# RaspiLabBoard.net
KiCad netlist of a schematic drawn in EAGLE
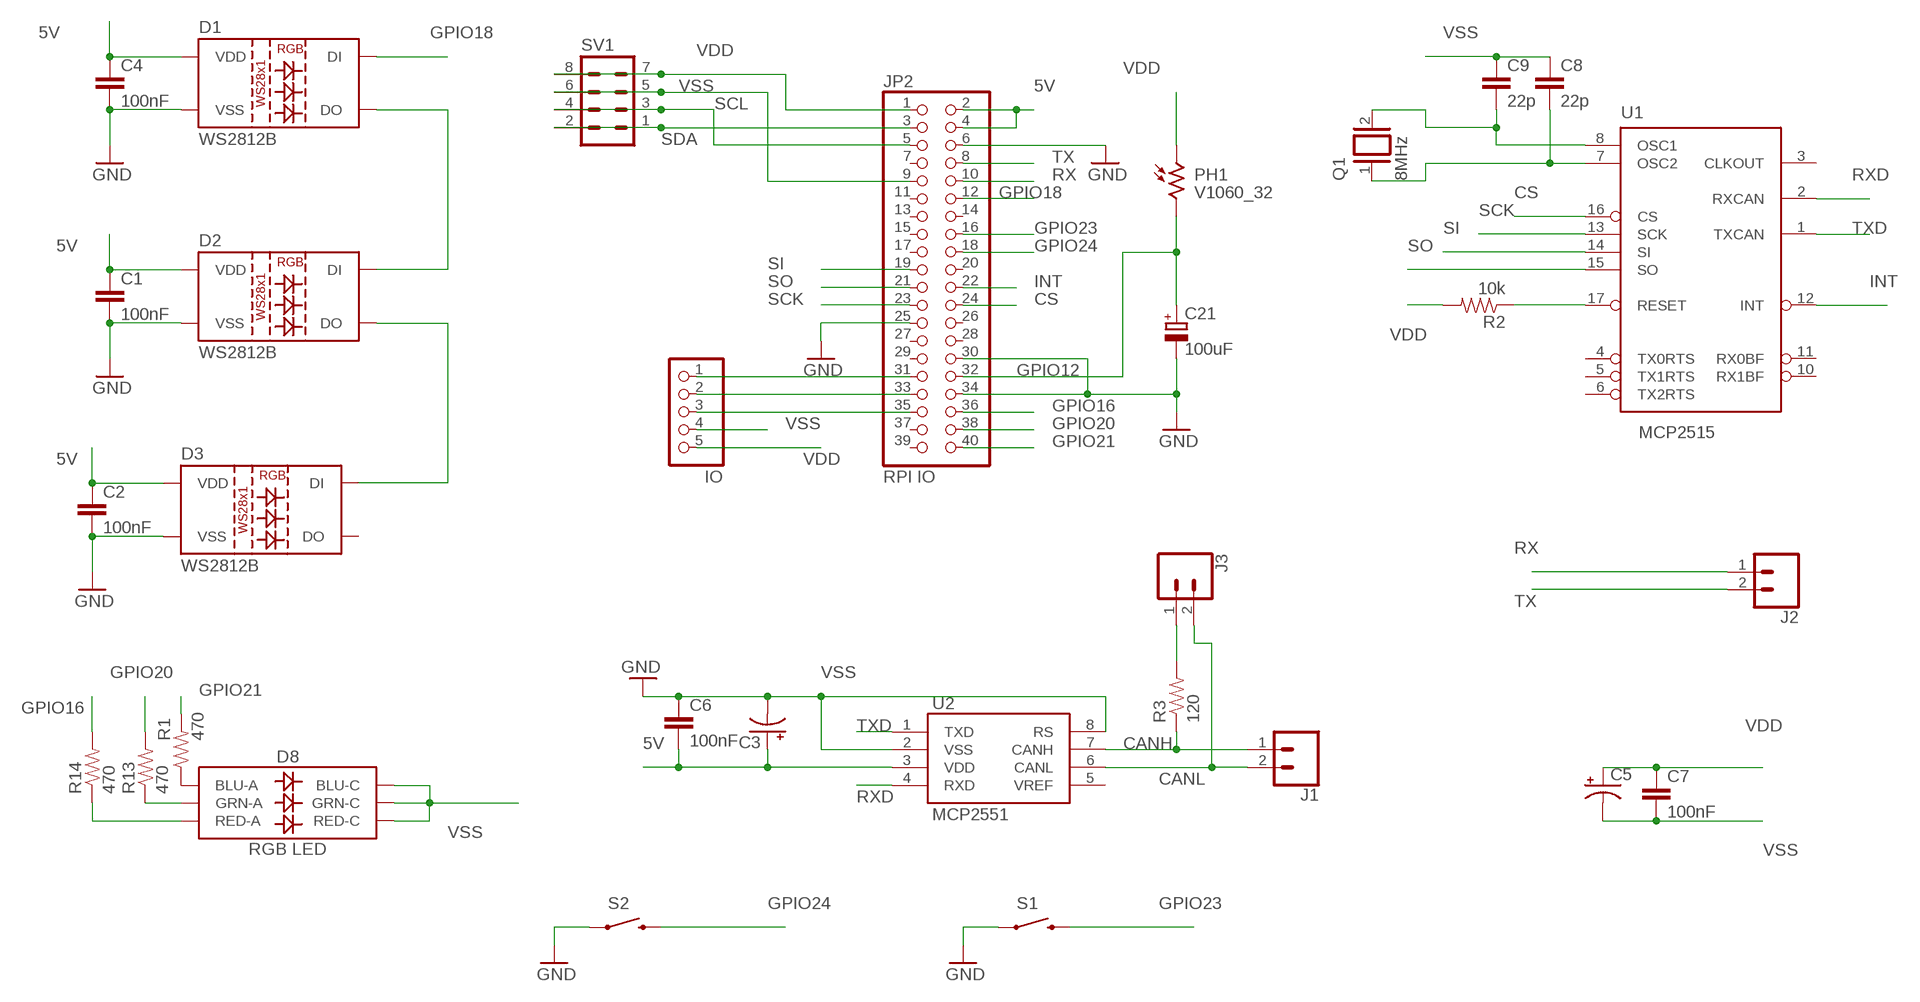
[diagram p0: schematic, sheet 1]

(export (version "E")
  (design (tool "Eeschema 10.0.6"))
  (components
    (comp (ref "C1")
      (value "100nF")
      (footprint "eagle-import:0805")
      (libsource (lib "eagle-import") (part "CAP0805"))
    )
    (comp (ref "C2")
      (value "100nF")
      (footprint "eagle-import:0805")
      (libsource (lib "eagle-import") (part "CAP0805"))
    )
    (comp (ref "C3")
      (value "CPOL-USE2-5")
      (footprint "eagle-import:E2-5")
      (libsource (lib "eagle-import") (part "CPOL-USE2-5"))
    )
    (comp (ref "C4")
      (value "100nF")
      (footprint "eagle-import:0805")
      (libsource (lib "eagle-import") (part "CAP0805"))
    )
    (comp (ref "C5")
      (value "CPOL-USE2-5")
      (footprint "eagle-import:E2-5")
      (libsource (lib "eagle-import") (part "CPOL-USE2-5"))
    )
    (comp (ref "C6")
      (value "100nF")
      (footprint "eagle-import:0805")
      (libsource (lib "eagle-import") (part "CAP0805"))
    )
    (comp (ref "C7")
      (value "100nF")
      (footprint "eagle-import:0805")
      (libsource (lib "eagle-import") (part "CAP0805"))
    )
    (comp (ref "C8")
      (value "22p")
      (footprint "eagle-import:0805")
      (libsource (lib "eagle-import") (part "CAP0805"))
    )
    (comp (ref "C9")
      (value "22p")
      (footprint "eagle-import:0805")
      (libsource (lib "eagle-import") (part "CAP0805"))
    )
    (comp (ref "C21")
      (value "100uF")
      (footprint "eagle-import:E5-10,5")
      (libsource (lib "eagle-import") (part "CPOL-EUE5-10.5"))
    )
    (comp (ref "D1")
      (value "WS2812B")
      (footprint "eagle-import:WS2812B")
      (libsource (lib "eagle-import") (part "WS2812B"))
    )
    (comp (ref "D2")
      (value "WS2812B")
      (footprint "eagle-import:WS2812B")
      (libsource (lib "eagle-import") (part "WS2812B"))
    )
    (comp (ref "D3")
      (value "WS2812B")
      (footprint "eagle-import:WS2812B")
      (libsource (lib "eagle-import") (part "WS2812B"))
    )
    (comp (ref "D8")
      (value "RGB LED")
      (footprint "eagle-import:LED-TRICOLOR-5050")
      (libsource (lib "eagle-import") (part "LED-RGBNO_IC"))
    )
    (comp (ref "J1")
      (value "CONN_02")
      (footprint "eagle-import:1X02")
      (libsource (lib "eagle-import") (part "CONN_02"))
    )
    (comp (ref "J2")
      (value "CONN_02")
      (footprint "eagle-import:1X02")
      (libsource (lib "eagle-import") (part "CONN_02"))
    )
    (comp (ref "J3")
      (value "CONN_02")
      (footprint "eagle-import:1X02")
      (libsource (lib "eagle-import") (part "CONN_02"))
    )
    (comp (ref "JP2")
      (value "RPI IO")
      (footprint "eagle-import:2X20")
      (libsource (lib "eagle-import") (part "PINHD-2X20"))
    )
    (comp (ref "JP4")
      (value "IO")
      (footprint "eagle-import:1X05")
      (libsource (lib "eagle-import") (part "PINHD-1X5"))
    )
    (comp (ref "PH1")
      (value "V1060_32")
      (footprint "eagle-import:TO-5_V10")
      (libsource (lib "eagle-import") (part "?1060V_32"))
    )
    (comp (ref "Q1")
      (value "8MHz")
      (footprint "eagle-import:QS")
      (libsource (lib "eagle-import") (part "XTAL/S"))
    )
    (comp (ref "R1")
      (value "470")
      (footprint "eagle-import:0805")
      (libsource (lib "eagle-import") (part "RESISTOR0805-RES"))
    )
    (comp (ref "R2")
      (value "10k")
      (footprint "eagle-import:0805")
      (libsource (lib "eagle-import") (part "RESISTOR0805-RES"))
    )
    (comp (ref "R3")
      (value "120")
      (footprint "eagle-import:0805")
      (libsource (lib "eagle-import") (part "RESISTOR0805-RES"))
    )
    (comp (ref "R13")
      (value "470")
      (footprint "eagle-import:0805")
      (libsource (lib "eagle-import") (part "RESISTOR0805-RES"))
    )
    (comp (ref "R14")
      (value "470")
      (footprint "eagle-import:0805")
      (libsource (lib "eagle-import") (part "RESISTOR0805-RES"))
    )
    (comp (ref "S1")
      (value "RESET")
      (footprint "eagle-import:TACTILE-SWITCH-1101NE")
      (libsource (lib "eagle-import") (part "SWITCH-MOMENTARY-2SMD-1101NE"))
    )
    (comp (ref "S2")
      (value "RESET")
      (footprint "eagle-import:TACTILE-SWITCH-1101NE")
      (libsource (lib "eagle-import") (part "SWITCH-MOMENTARY-2SMD-1101NE"))
    )
    (comp (ref "SV1")
      (value "MA04-2")
      (footprint "eagle-import:MA04-2")
      (libsource (lib "eagle-import") (part "MA04-2"))
    )
    (comp (ref "U1")
      (value "MCP2515")
      (footprint "eagle-import:SO18W")
      (fields (field (name "SPICEPREFIX") "X"))
      (libsource (lib "eagle-import") (part "MCP2515(MCP2510)SO"))
    )
    (comp (ref "U2")
      (value "MCP2551")
      (footprint "eagle-import:SO08")
      (libsource (lib "eagle-import") (part "MCP2551"))
    )
  )
  (nets
    (net (code "1") (name "/5V") (class "Default")
      (node (ref "C1") (pin "1") (pinfunction "1_1") (pintype "passive"))
      (node (ref "C2") (pin "1") (pinfunction "1_1") (pintype "passive"))
      (node (ref "C3") (pin "+") (pinfunction "+_+") (pintype "passive"))
      (node (ref "C4") (pin "1") (pinfunction "1_1") (pintype "passive"))
      (node (ref "C6") (pin "2") (pinfunction "2_2") (pintype "passive"))
      (node (ref "D1") (pin "1") (pinfunction "VDD_1") (pintype "bidirectional"))
      (node (ref "D2") (pin "1") (pinfunction "VDD_1") (pintype "bidirectional"))
      (node (ref "D3") (pin "1") (pinfunction "VDD_1") (pintype "bidirectional"))
      (node (ref "JP2") (pin "2") (pinfunction "2_2") (pintype "passive"))
      (node (ref "JP2") (pin "4") (pinfunction "4_4") (pintype "passive"))
      (node (ref "U2") (pin "3") (pinfunction "VDD_3") (pintype "bidirectional"))
    )
    (net (code "2") (name "/CANH") (class "Default")
      (node (ref "J1") (pin "1") (pinfunction "1_1") (pintype "passive"))
      (node (ref "R3") (pin "1") (pinfunction "1_1") (pintype "passive"))
      (node (ref "U2") (pin "7") (pinfunction "CANH_7") (pintype "bidirectional"))
    )
    (net (code "3") (name "/CANL") (class "Default")
      (node (ref "J1") (pin "2") (pinfunction "2_2") (pintype "passive"))
      (node (ref "J3") (pin "2") (pinfunction "2_2") (pintype "passive"))
      (node (ref "U2") (pin "6") (pinfunction "CANL_6") (pintype "bidirectional"))
    )
    (net (code "4") (name "/CS") (class "Default")
      (node (ref "JP2") (pin "24") (pinfunction "24_24") (pintype "passive"))
      (node (ref "U1") (pin "16") (pinfunction "CS_16") (pintype "input"))
    )
    (net (code "5") (name "/GPIO12") (class "Default")
      (node (ref "C21") (pin "+") (pinfunction "+_+") (pintype "passive"))
      (node (ref "JP2") (pin "32") (pinfunction "32_32") (pintype "passive"))
      (node (ref "PH1") (pin "2") (pinfunction "2_2") (pintype "passive"))
    )
    (net (code "6") (name "/GPIO16") (class "Default")
      (node (ref "JP2") (pin "36") (pinfunction "36_36") (pintype "passive"))
      (node (ref "R14") (pin "2") (pinfunction "2_2") (pintype "passive"))
    )
    (net (code "7") (name "/GPIO18") (class "Default")
      (node (ref "D1") (pin "4") (pinfunction "DI_4") (pintype "bidirectional"))
      (node (ref "JP2") (pin "12") (pinfunction "12_12") (pintype "passive"))
    )
    (net (code "8") (name "/GPIO20") (class "Default")
      (node (ref "JP2") (pin "38") (pinfunction "38_38") (pintype "passive"))
      (node (ref "R13") (pin "2") (pinfunction "2_2") (pintype "passive"))
    )
    (net (code "9") (name "/GPIO21") (class "Default")
      (node (ref "JP2") (pin "40") (pinfunction "40_40") (pintype "passive"))
      (node (ref "R1") (pin "2") (pinfunction "2_2") (pintype "passive"))
    )
    (net (code "10") (name "/GPIO23") (class "Default")
      (node (ref "JP2") (pin "16") (pinfunction "16_16") (pintype "passive"))
      (node (ref "S1") (pin "2") (pinfunction "2_2") (pintype "passive"))
    )
    (net (code "11") (name "/GPIO24") (class "Default")
      (node (ref "JP2") (pin "18") (pinfunction "18_18") (pintype "passive"))
      (node (ref "S2") (pin "2") (pinfunction "2_2") (pintype "passive"))
    )
    (net (code "12") (name "/INT") (class "Default")
      (node (ref "JP2") (pin "22") (pinfunction "22_22") (pintype "passive"))
      (node (ref "U1") (pin "12") (pinfunction "INT_12") (pintype "output"))
    )
    (net (code "13") (name "/RX") (class "Default")
      (node (ref "J2") (pin "1") (pinfunction "1_1") (pintype "passive"))
      (node (ref "JP2") (pin "10") (pinfunction "10_10") (pintype "passive"))
    )
    (net (code "14") (name "/RXD") (class "Default")
      (node (ref "U1") (pin "2") (pinfunction "RXCAN_2") (pintype "input"))
      (node (ref "U2") (pin "4") (pinfunction "RXD_4") (pintype "bidirectional"))
    )
    (net (code "15") (name "/SCK") (class "Default")
      (node (ref "JP2") (pin "23") (pinfunction "23_23") (pintype "passive"))
      (node (ref "U1") (pin "13") (pinfunction "SCK_13") (pintype "input"))
    )
    (net (code "16") (name "/SCL") (class "Default")
      (node (ref "JP2") (pin "5") (pinfunction "5_5") (pintype "passive"))
      (node (ref "SV1") (pin "3") (pinfunction "3_3") (pintype "passive"))
      (node (ref "SV1") (pin "4") (pinfunction "4_4") (pintype "passive"))
    )
    (net (code "17") (name "/SDA") (class "Default")
      (node (ref "JP2") (pin "3") (pinfunction "3_3") (pintype "passive"))
      (node (ref "SV1") (pin "1") (pinfunction "1_1") (pintype "passive"))
      (node (ref "SV1") (pin "2") (pinfunction "2_2") (pintype "passive"))
    )
    (net (code "18") (name "/SI") (class "Default")
      (node (ref "JP2") (pin "19") (pinfunction "19_19") (pintype "passive"))
      (node (ref "U1") (pin "14") (pinfunction "SI_14") (pintype "input"))
    )
    (net (code "19") (name "/SO") (class "Default")
      (node (ref "JP2") (pin "21") (pinfunction "21_21") (pintype "passive"))
      (node (ref "U1") (pin "15") (pinfunction "SO_15") (pintype "output"))
    )
    (net (code "20") (name "/TX") (class "Default")
      (node (ref "J2") (pin "2") (pinfunction "2_2") (pintype "passive"))
      (node (ref "JP2") (pin "8") (pinfunction "8_8") (pintype "passive"))
    )
    (net (code "21") (name "/TXD") (class "Default")
      (node (ref "U1") (pin "1") (pinfunction "TXCAN_1") (pintype "output"))
      (node (ref "U2") (pin "1") (pinfunction "TXD_1") (pintype "bidirectional"))
    )
    (net (code "22") (name "/VDD") (class "Default")
      (node (ref "C5") (pin "+") (pinfunction "+_+") (pintype "passive"))
      (node (ref "C7") (pin "1") (pinfunction "1_1") (pintype "passive"))
      (node (ref "JP2") (pin "1") (pinfunction "1_1") (pintype "passive"))
      (node (ref "JP4") (pin "5") (pinfunction "5_5") (pintype "passive"))
      (node (ref "PH1") (pin "1") (pinfunction "1_1") (pintype "passive"))
      (node (ref "R2") (pin "2") (pinfunction "2_2") (pintype "passive"))
      (node (ref "SV1") (pin "7") (pinfunction "7_7") (pintype "passive"))
      (node (ref "SV1") (pin "8") (pinfunction "8_8") (pintype "passive"))
    )
    (net (code "23") (name "GND") (class "Default")
      (node (ref "C1") (pin "2") (pinfunction "2_2") (pintype "passive"))
      (node (ref "C2") (pin "2") (pinfunction "2_2") (pintype "passive"))
      (node (ref "C21") (pin "-") (pinfunction "-_-") (pintype "passive"))
      (node (ref "C3") (pin "-") (pinfunction "-_-") (pintype "passive"))
      (node (ref "C4") (pin "2") (pinfunction "2_2") (pintype "passive"))
      (node (ref "C5") (pin "-") (pinfunction "-_-") (pintype "passive"))
      (node (ref "C6") (pin "1") (pinfunction "1_1") (pintype "passive"))
      (node (ref "C7") (pin "2") (pinfunction "2_2") (pintype "passive"))
      (node (ref "C8") (pin "1") (pinfunction "1_1") (pintype "passive"))
      (node (ref "C9") (pin "1") (pinfunction "1_1") (pintype "passive"))
      (node (ref "D1") (pin "3") (pinfunction "VSS_3") (pintype "bidirectional"))
      (node (ref "D2") (pin "3") (pinfunction "VSS_3") (pintype "bidirectional"))
      (node (ref "D3") (pin "3") (pinfunction "VSS_3") (pintype "bidirectional"))
      (node (ref "D8") (pin "4") (pinfunction "BLU-C_4") (pintype "bidirectional"))
      (node (ref "D8") (pin "5") (pinfunction "RED-C_5") (pintype "bidirectional"))
      (node (ref "D8") (pin "6") (pinfunction "GRN-C_6") (pintype "bidirectional"))
      (node (ref "JP2") (pin "25") (pinfunction "25_25") (pintype "passive"))
      (node (ref "JP2") (pin "30") (pinfunction "30_30") (pintype "passive"))
      (node (ref "JP2") (pin "34") (pinfunction "34_34") (pintype "passive"))
      (node (ref "JP2") (pin "6") (pinfunction "6_6") (pintype "passive"))
      (node (ref "JP2") (pin "9") (pinfunction "9_9") (pintype "passive"))
      (node (ref "JP4") (pin "4") (pinfunction "4_4") (pintype "passive"))
      (node (ref "S1") (pin "1") (pinfunction "1_1") (pintype "passive"))
      (node (ref "S2") (pin "1") (pinfunction "1_1") (pintype "passive"))
      (node (ref "SV1") (pin "5") (pinfunction "5_5") (pintype "passive"))
      (node (ref "SV1") (pin "6") (pinfunction "6_6") (pintype "passive"))
      (node (ref "U2") (pin "2") (pinfunction "VSS_2") (pintype "bidirectional"))
      (node (ref "U2") (pin "8") (pinfunction "RS_8") (pintype "bidirectional"))
    )
    (net (code "24") (name "Net-(D1-DO)") (class "Default")
      (node (ref "D1") (pin "2") (pinfunction "DO_2") (pintype "bidirectional"))
      (node (ref "D2") (pin "4") (pinfunction "DI_4") (pintype "bidirectional"))
    )
    (net (code "25") (name "Net-(D2-DO)") (class "Default")
      (node (ref "D2") (pin "2") (pinfunction "DO_2") (pintype "bidirectional"))
      (node (ref "D3") (pin "4") (pinfunction "DI_4") (pintype "bidirectional"))
    )
    (net (code "26") (name "Net-(D8-BLU-A)") (class "Default")
      (node (ref "D8") (pin "3") (pinfunction "BLU-A_3") (pintype "bidirectional"))
      (node (ref "R1") (pin "1") (pinfunction "1_1") (pintype "passive"))
    )
    (net (code "27") (name "Net-(D8-GRN-A)") (class "Default")
      (node (ref "D8") (pin "1") (pinfunction "GRN-A_1") (pintype "bidirectional"))
      (node (ref "R13") (pin "1") (pinfunction "1_1") (pintype "passive"))
    )
    (net (code "28") (name "Net-(D8-RED-A)") (class "Default")
      (node (ref "D8") (pin "2") (pinfunction "RED-A_2") (pintype "bidirectional"))
      (node (ref "R14") (pin "1") (pinfunction "1_1") (pintype "passive"))
    )
    (net (code "29") (name "Net-(J3-Pad1)") (class "Default")
      (node (ref "J3") (pin "1") (pinfunction "1_1") (pintype "passive"))
      (node (ref "R3") (pin "2") (pinfunction "2_2") (pintype "passive"))
    )
    (net (code "30") (name "Net-(JP2-Pad31)") (class "Default")
      (node (ref "JP2") (pin "31") (pinfunction "31_31") (pintype "passive"))
      (node (ref "JP4") (pin "1") (pinfunction "1_1") (pintype "passive"))
    )
    (net (code "31") (name "Net-(JP2-Pad33)") (class "Default")
      (node (ref "JP2") (pin "33") (pinfunction "33_33") (pintype "passive"))
      (node (ref "JP4") (pin "2") (pinfunction "2_2") (pintype "passive"))
    )
    (net (code "32") (name "Net-(JP2-Pad35)") (class "Default")
      (node (ref "JP2") (pin "35") (pinfunction "35_35") (pintype "passive"))
      (node (ref "JP4") (pin "3") (pinfunction "3_3") (pintype "passive"))
    )
    (net (code "33") (name "Net-(U1A-OSC1)") (class "Default")
      (node (ref "C9") (pin "2") (pinfunction "2_2") (pintype "passive"))
      (node (ref "Q1") (pin "2") (pinfunction "2_2") (pintype "passive"))
      (node (ref "U1") (pin "8") (pinfunction "OSC1_8") (pintype "input"))
    )
    (net (code "34") (name "Net-(U1A-OSC2)") (class "Default")
      (node (ref "C8") (pin "2") (pinfunction "2_2") (pintype "passive"))
      (node (ref "Q1") (pin "1") (pinfunction "1_1") (pintype "passive"))
      (node (ref "U1") (pin "7") (pinfunction "OSC2_7") (pintype "output"))
    )
    (net (code "35") (name "Net-(U1A-RESET)") (class "Default")
      (node (ref "R2") (pin "1") (pinfunction "1_1") (pintype "passive"))
      (node (ref "U1") (pin "17") (pinfunction "RESET_17") (pintype "input"))
    )
    (net (code "36") (name "unconnected-(D3-DO-Pad2)") (class "Default")
      (node (ref "D3") (pin "2") (pinfunction "DO_2") (pintype "bidirectional"))
    )
    (net (code "37") (name "unconnected-(JP2-Pad7)") (class "Default")
      (node (ref "JP2") (pin "7") (pinfunction "7_7") (pintype "passive"))
    )
    (net (code "38") (name "unconnected-(JP2-Pad11)") (class "Default")
      (node (ref "JP2") (pin "11") (pinfunction "11_11") (pintype "passive"))
    )
    (net (code "39") (name "unconnected-(JP2-Pad13)") (class "Default")
      (node (ref "JP2") (pin "13") (pinfunction "13_13") (pintype "passive"))
    )
    (net (code "40") (name "unconnected-(JP2-Pad14)") (class "Default")
      (node (ref "JP2") (pin "14") (pinfunction "14_14") (pintype "passive"))
    )
    (net (code "41") (name "unconnected-(JP2-Pad15)") (class "Default")
      (node (ref "JP2") (pin "15") (pinfunction "15_15") (pintype "passive"))
    )
    (net (code "42") (name "unconnected-(JP2-Pad17)") (class "Default")
      (node (ref "JP2") (pin "17") (pinfunction "17_17") (pintype "passive"))
    )
    (net (code "43") (name "unconnected-(JP2-Pad20)") (class "Default")
      (node (ref "JP2") (pin "20") (pinfunction "20_20") (pintype "passive"))
    )
    (net (code "44") (name "unconnected-(JP2-Pad26)") (class "Default")
      (node (ref "JP2") (pin "26") (pinfunction "26_26") (pintype "passive"))
    )
    (net (code "45") (name "unconnected-(JP2-Pad27)") (class "Default")
      (node (ref "JP2") (pin "27") (pinfunction "27_27") (pintype "passive"))
    )
    (net (code "46") (name "unconnected-(JP2-Pad28)") (class "Default")
      (node (ref "JP2") (pin "28") (pinfunction "28_28") (pintype "passive"))
    )
    (net (code "47") (name "unconnected-(JP2-Pad29)") (class "Default")
      (node (ref "JP2") (pin "29") (pinfunction "29_29") (pintype "passive"))
    )
    (net (code "48") (name "unconnected-(JP2-Pad37)") (class "Default")
      (node (ref "JP2") (pin "37") (pinfunction "37_37") (pintype "passive"))
    )
    (net (code "49") (name "unconnected-(JP2-Pad39)") (class "Default")
      (node (ref "JP2") (pin "39") (pinfunction "39_39") (pintype "passive"))
    )
    (net (code "50") (name "unconnected-(U1A-CLKOUT-Pad3)") (class "Default")
      (node (ref "U1") (pin "3") (pinfunction "CLKOUT_3") (pintype "output"))
    )
    (net (code "51") (name "unconnected-(U1A-RX0BF-Pad11)") (class "Default")
      (node (ref "U1") (pin "11") (pinfunction "RX0BF_11") (pintype "output"))
    )
    (net (code "52") (name "unconnected-(U1A-RX1BF-Pad10)") (class "Default")
      (node (ref "U1") (pin "10") (pinfunction "RX1BF_10") (pintype "output"))
    )
    (net (code "53") (name "unconnected-(U1A-TX0RTS-Pad4)") (class "Default")
      (node (ref "U1") (pin "4") (pinfunction "TX0RTS_4") (pintype "input"))
    )
    (net (code "54") (name "unconnected-(U1A-TX1RTS-Pad5)") (class "Default")
      (node (ref "U1") (pin "5") (pinfunction "TX1RTS_5") (pintype "input"))
    )
    (net (code "55") (name "unconnected-(U1A-TX2RTS-Pad6)") (class "Default")
      (node (ref "U1") (pin "6") (pinfunction "TX2RTS_6") (pintype "input"))
    )
    (net (code "56") (name "unconnected-(U2-VREF-Pad5)") (class "Default")
      (node (ref "U2") (pin "5") (pinfunction "VREF_5") (pintype "bidirectional"))
    )
  )
)
